# S03-MICROPHONE.net
KiCad netlist of a schematic drawn in Altium Designer
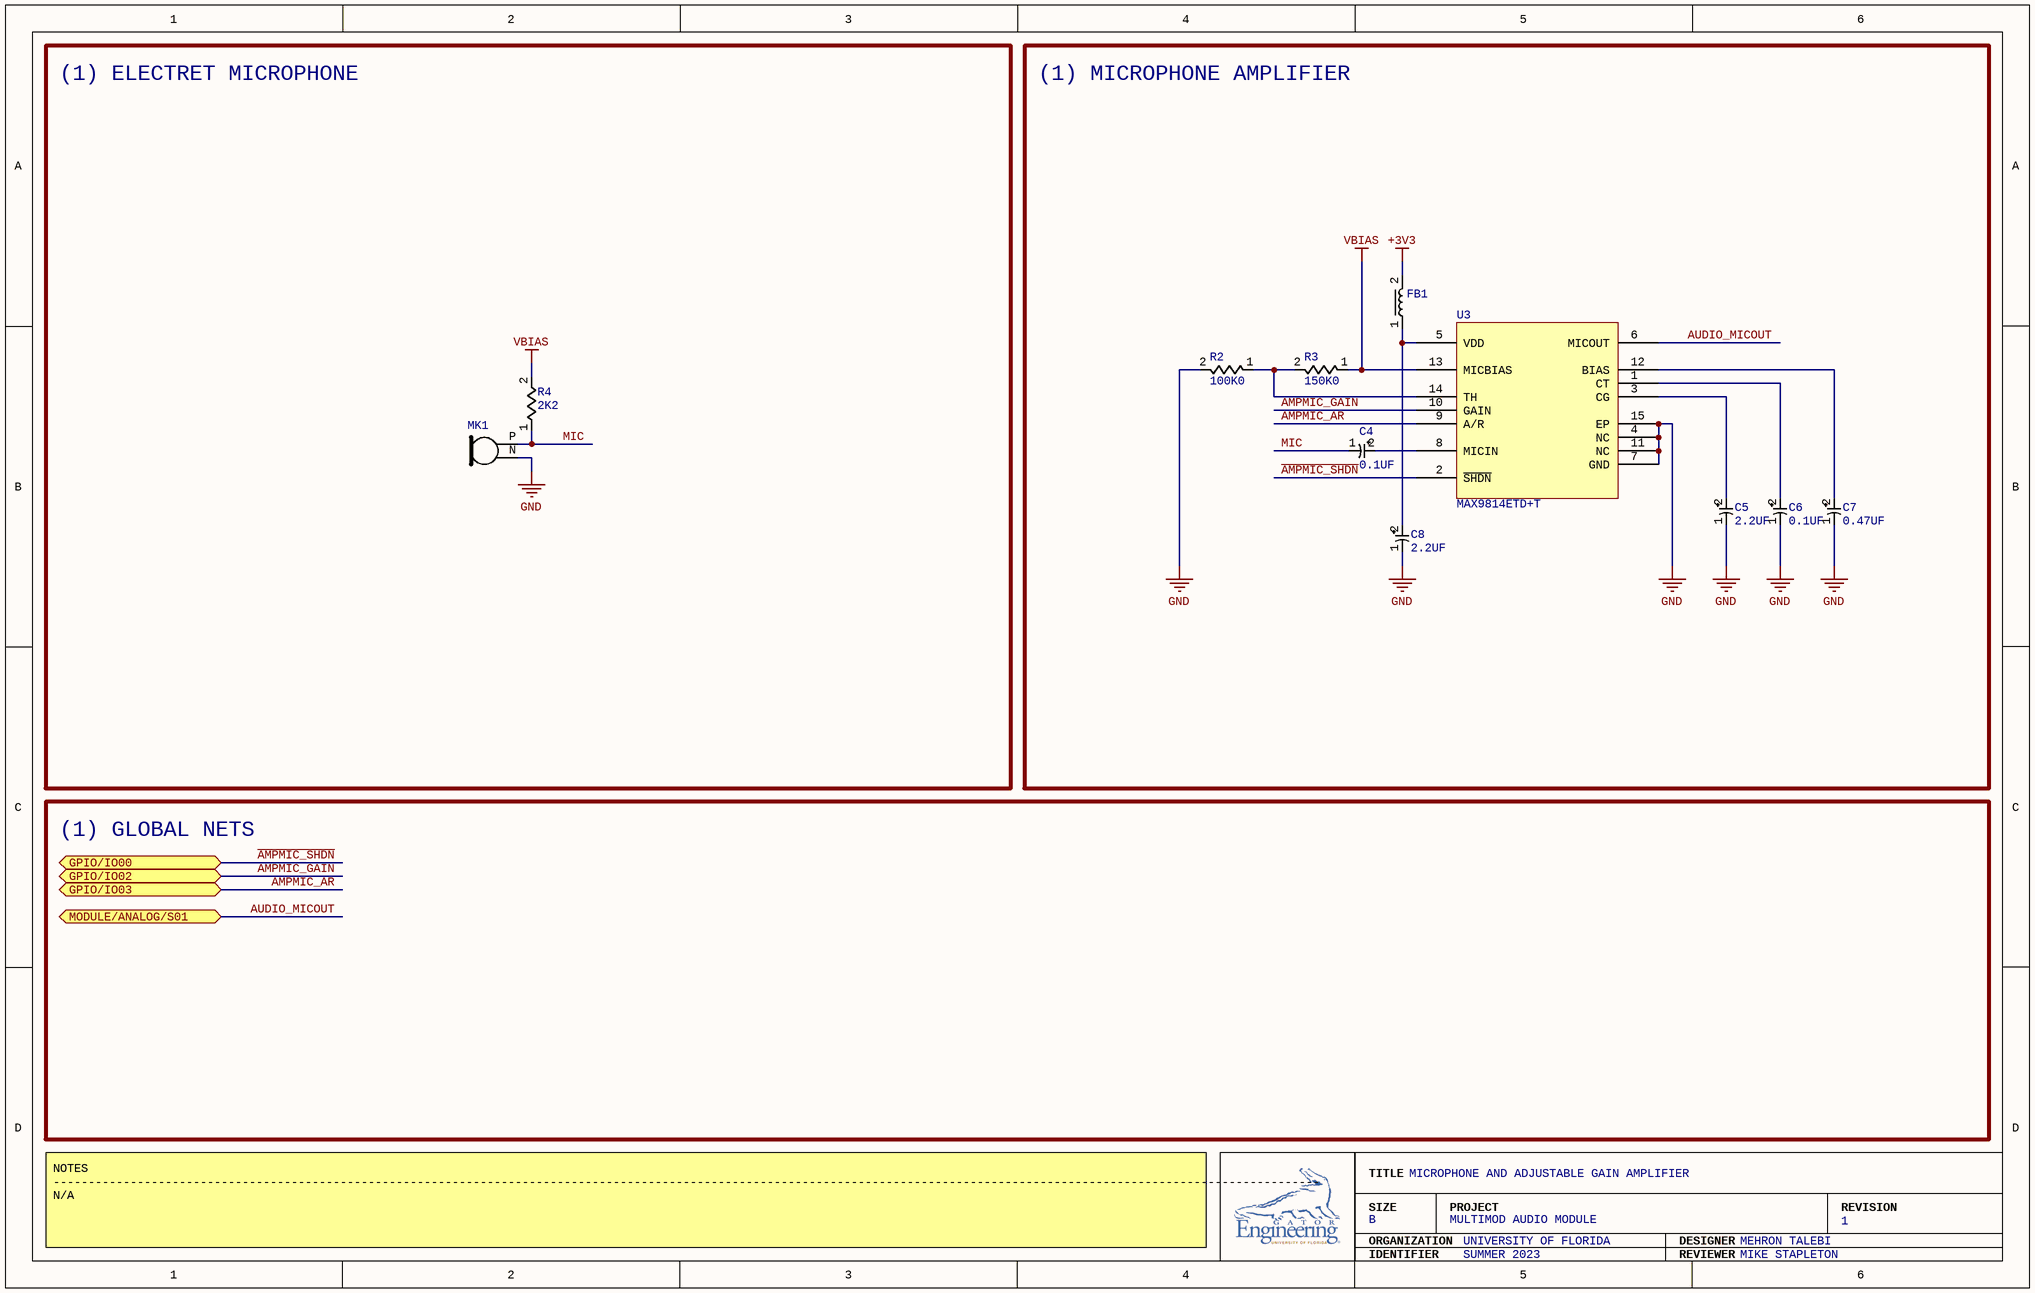
[diagram p0: S03-MICROPHONE.SchDoc]

(export (version "E")
  (design (tool "Eeschema 10.0.6"))
  (components
    (comp (ref "C4")
      (value "0.1UF")
      (footprint "TAJR104K035RNJ")
      (description "CAP TANT 0.1UF 10% 35V 0805")
      (fields (field (name "TOLERANCE") "±10%"))
      (libsource (lib "") (part "TAJR104K035RNJ_1"))
    )
    (comp (ref "C5")
      (value "2.2UF")
      (footprint "TAJR225K020RNJ")
      (description "CAP TANT 2.2UF 10% 20V 0805")
      (fields (field (name "TOLERANCE") "±10%"))
      (libsource (lib "Master") (part "TAJR225K020RNJ"))
    )
    (comp (ref "C6")
      (value "0.1UF")
      (footprint "TAJR104K035RNJ")
      (description "CAP TANT 0.1UF 10% 35V 0805")
      (fields (field (name "TOLERANCE") "±10%"))
      (libsource (lib "Master") (part "TAJR104K035RNJ"))
    )
    (comp (ref "C7")
      (value "0.47UF")
      (footprint "TAJR474K020RNJ")
      (description "CAP TANT 0.47UF 10% 20V 0805")
      (fields (field (name "TOLERANCE") "±10%"))
      (libsource (lib "Master") (part "TAJR474K020RNJ"))
    )
    (comp (ref "C8")
      (value "2.2UF")
      (footprint "TAJR225K020RNJ")
      (description "CAP TANT 2.2UF 10% 20V 0805")
      (fields (field (name "TOLERANCE") "±10%"))
      (libsource (lib "Master") (part "TAJR225K020RNJ"))
    )
    (comp (ref "FB1")
      (value "ILBB0805ER102V")
      (footprint "ILBB0805ER102V")
      (description "FERRITE BEAD 1K OHM 0805 1LN")
      (libsource (lib "Master") (part "ILBB0805ER102V"))
    )
    (comp (ref "MK1")
      (value "CMA-4544PF-W")
      (footprint "CMA-4544PF-W")
      (description "MIC COND ANLG OMNI -44DB 0.382\"D")
      (libsource (lib "Master") (part "CMA-4544PF-W"))
    )
    (comp (ref "R2")
      (value "100K0")
      (footprint "RC0805FR-7W100KL")
      (description "RES 100K OHM 1% 1/4W 0805")
      (fields (field (name "TOLERANCE") "±1%"))
      (libsource (lib "Master") (part "RC0805FR-7W100KL"))
    )
    (comp (ref "R3")
      (value "150K0")
      (footprint "RC0805FR-07150KL")
      (description "RES 150K OHM 1% 1/8W 0805")
      (fields (field (name "TOLERANCE") "±1%"))
      (libsource (lib "Master") (part "RC0805FR-07150KL"))
    )
    (comp (ref "R4")
      (value "2K2")
      (footprint "RC0805FR-072K2L")
      (description "RES 2.2K OHM 1% 1/8W 0805")
      (fields (field (name "TOLERANCE") "±1%"))
      (libsource (lib "Master") (part "RC0805FR-072K2L"))
    )
    (comp (ref "U3")
      (value "MAX9814ETD+T")
      (footprint "MAX9814ETD+T")
      (description "IC AMP CLASS AB MONO 14TDFN")
      (libsource (lib "Master") (part "MAX9814ETD+T"))
    )
  )
  (nets
    (net (code "1") (name "+3V3") (class "Default")
      (node (ref "FB1") (pin "2") (pinfunction "2_2") (pintype "passive"))
    )
    (net (code "2") (name "/AMPMIC_AR") (class "Default")
      (node (ref "U3") (pin "9") (pinfunction "A/R_9") (pintype "passive"))
    )
    (net (code "3") (name "/AMPMIC_GAIN") (class "Default")
      (node (ref "U3") (pin "10") (pinfunction "GAIN_10") (pintype "passive"))
    )
    (net (code "4") (name "/AMPMIC_SHDN") (class "Default")
      (node (ref "U3") (pin "2") (pinfunction "SHDN_2") (pintype "passive"))
    )
    (net (code "5") (name "/AUDIO_MICOUT") (class "Default")
      (node (ref "U3") (pin "6") (pinfunction "MICOUT_6") (pintype "passive"))
    )
    (net (code "6") (name "/MIC") (class "Default")
      (node (ref "C4") (pin "1") (pinfunction "1_1") (pintype "passive"))
      (node (ref "MK1") (pin "P") (pinfunction "P_P") (pintype "passive"))
      (node (ref "R4") (pin "1") (pinfunction "1_1") (pintype "passive"))
    )
    (net (code "7") (name "GND") (class "Default")
      (node (ref "C5") (pin "1") (pinfunction "1_1") (pintype "passive"))
      (node (ref "C6") (pin "1") (pinfunction "1_1") (pintype "passive"))
      (node (ref "C7") (pin "1") (pinfunction "1_1") (pintype "passive"))
      (node (ref "C8") (pin "1") (pinfunction "1_1") (pintype "passive"))
      (node (ref "MK1") (pin "N") (pinfunction "N_N") (pintype "passive"))
      (node (ref "R2") (pin "2") (pinfunction "2_2") (pintype "passive"))
      (node (ref "U3") (pin "11") (pinfunction "NC_11") (pintype "passive"))
      (node (ref "U3") (pin "15") (pinfunction "EP_15") (pintype "passive"))
      (node (ref "U3") (pin "4") (pinfunction "NC_4") (pintype "passive"))
      (node (ref "U3") (pin "7") (pinfunction "GND_7") (pintype "passive"))
    )
    (net (code "8") (name "Net-(U3-BIAS)") (class "Default")
      (node (ref "C7") (pin "2") (pinfunction "2_2") (pintype "passive"))
      (node (ref "U3") (pin "12") (pinfunction "BIAS_12") (pintype "passive"))
    )
    (net (code "9") (name "Net-(U3-CG)") (class "Default")
      (node (ref "C5") (pin "2") (pinfunction "2_2") (pintype "passive"))
      (node (ref "U3") (pin "3") (pinfunction "CG_3") (pintype "passive"))
    )
    (net (code "10") (name "Net-(U3-CT)") (class "Default")
      (node (ref "C6") (pin "2") (pinfunction "2_2") (pintype "passive"))
      (node (ref "U3") (pin "1") (pinfunction "CT_1") (pintype "passive"))
    )
    (net (code "11") (name "Net-(U3-MICIN)") (class "Default")
      (node (ref "C4") (pin "2") (pinfunction "2_2") (pintype "passive"))
      (node (ref "U3") (pin "8") (pinfunction "MICIN_8") (pintype "passive"))
    )
    (net (code "12") (name "Net-(U3-TH)") (class "Default")
      (node (ref "R2") (pin "1") (pinfunction "1_1") (pintype "passive"))
      (node (ref "R3") (pin "2") (pinfunction "2_2") (pintype "passive"))
      (node (ref "U3") (pin "14") (pinfunction "TH_14") (pintype "passive"))
    )
    (net (code "13") (name "Net-(U3-VDD)") (class "Default")
      (node (ref "C8") (pin "2") (pinfunction "2_2") (pintype "passive"))
      (node (ref "FB1") (pin "1") (pinfunction "1_1") (pintype "passive"))
      (node (ref "U3") (pin "5") (pinfunction "VDD_5") (pintype "passive"))
    )
    (net (code "14") (name "VBIAS") (class "Default")
      (node (ref "R3") (pin "1") (pinfunction "1_1") (pintype "passive"))
      (node (ref "R4") (pin "2") (pinfunction "2_2") (pintype "passive"))
      (node (ref "U3") (pin "13") (pinfunction "MICBIAS_13") (pintype "passive"))
    )
  )
)
